# Power.net
KiCad netlist of a schematic drawn in Altium Designer
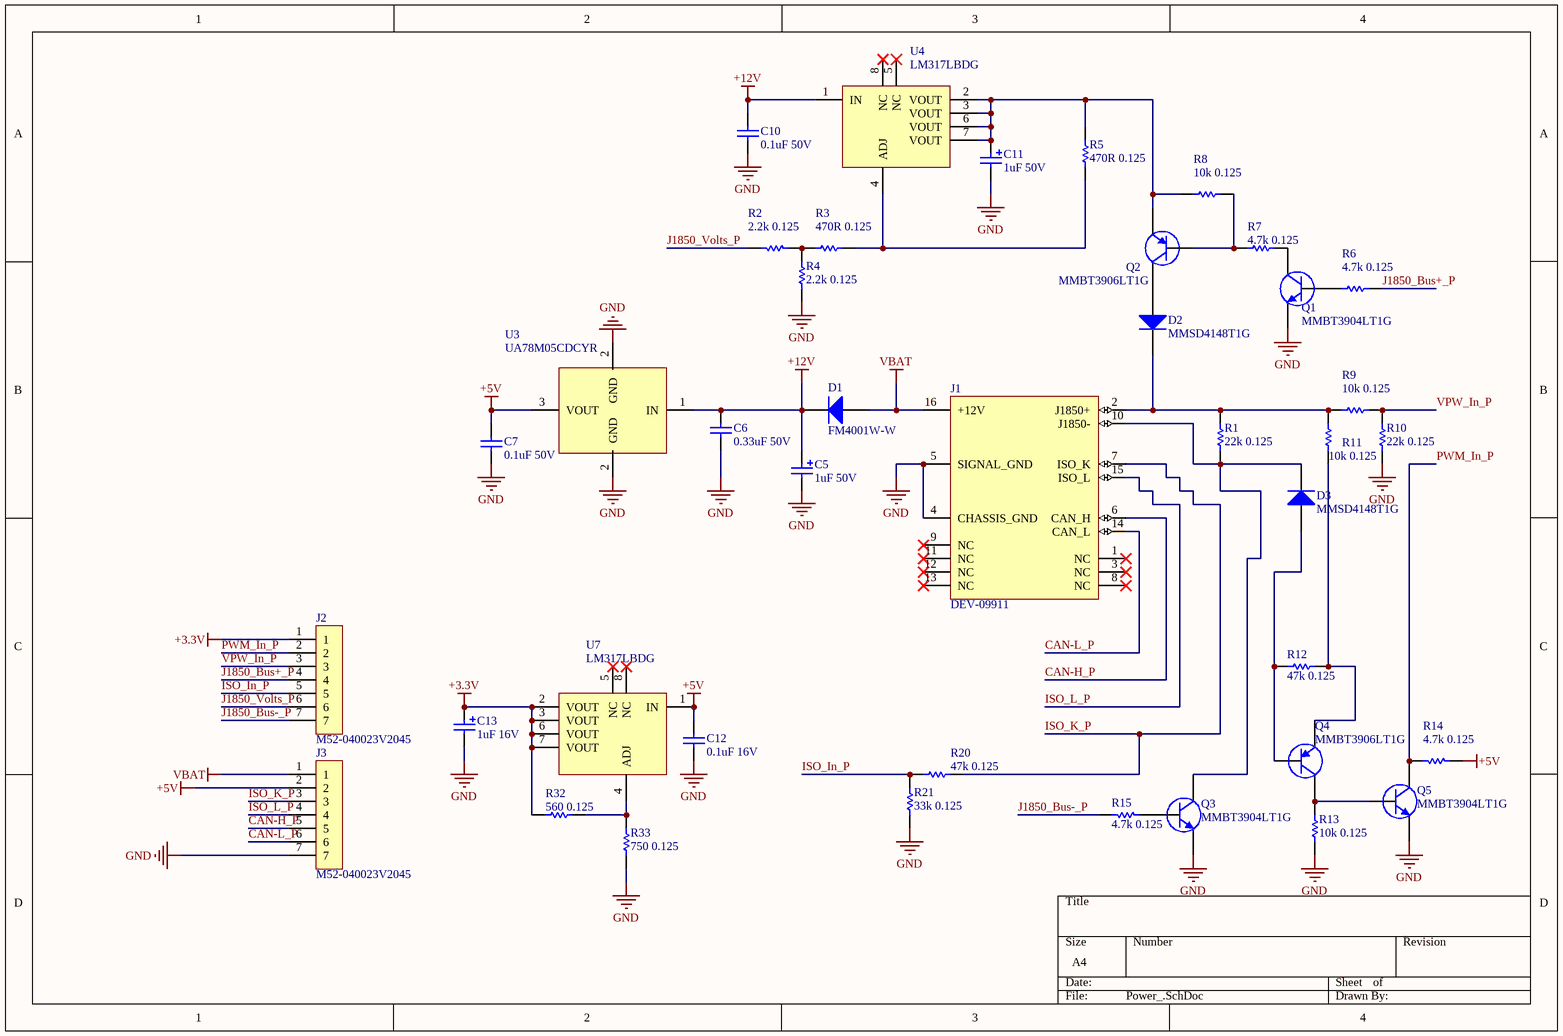
[diagram p0: Power_.SchDoc]

(export (version "E")
  (design (tool "Eeschema 10.0.6"))
  (components
    (comp (ref "C5")
      (value "1uF 50V")
      (footprint "C1005")
      (description "Surface-Mount Electrolitic Tantalum Capacitor, 1uF, 20% Tolerance, 1005 Size, 50V")
      (fields (field (name "PUBLISHER") "Altium Limited"))
      (libsource (lib "OBDII-components") (part "298D105X0050P2T"))
    )
    (comp (ref "C6")
      (value "0.33uF 50V")
      (footprint "1608[0603]")
      (description "Surface-Mount Ceramic Multilayer Capacitor, 0.33uF, 10% Tolerance, 0603 Size, 50V")
      (libsource (lib "OBDII-components") (part "C1608X7R1H334K080AC"))
    )
    (comp (ref "C7")
      (value "0.1uF 50V")
      (footprint "1608[0603]")
      (description "Surface-Mount Ceramic Multilayer Capacitor, 0.1uF, 10% Tolerance, 0603 Size, 50V")
      (libsource (lib "OBDII-components") (part "C0603C104K5RACTU"))
    )
    (comp (ref "C10")
      (value "0.1uF 50V")
      (footprint "1608[0603]")
      (description "Surface-Mount Ceramic Multilayer Capacitor, 0.1uF, 10% Tolerance, 0603 Size, 50V")
      (libsource (lib "OBDII-components") (part "C0603C104K5RACTU"))
    )
    (comp (ref "C11")
      (value "1uF 50V")
      (footprint "C1005")
      (description "Surface-Mount Electrolitic Tantalum Capacitor, 1uF, 20% Tolerance, 1005 Size, 50V")
      (fields (field (name "PUBLISHER") "Altium Limited"))
      (libsource (lib "OBDII-components") (part "298D105X0050P2T"))
    )
    (comp (ref "C12")
      (value "0.1uF 16V")
      (footprint "1608[0603]")
      (description "Surface-Mount Ceramic Multilayer Capacitor, 0.1uF, X5R, 10% Tolerance, 0603 Size, 16V")
      (fields (field (name "PUBLISHER") "Altium Limited"))
      (libsource (lib "OBDII-components") (part "GRM188R61C104KA01D"))
    )
    (comp (ref "C13")
      (value "1uF 16V")
      (footprint "C0603")
      (description "Surface-Mount Electrolitic Tantalum Capacitor, 1uF, 10% Tolerance, 0603 Size, 16V")
      (fields (field (name "PUBLISHER") "Altium Limited"))
      (libsource (lib "OBDII-components") (part "298D105X9016M2T"))
    )
    (comp (ref "D1")
      (value "FM4001W-W")
      (footprint "SMA,2.8mm")
      (description "1 Amp 50V  Rectifier")
      (libsource (lib "OBDII-components") (part "FM4001W-W"))
    )
    (comp (ref "D2")
      (value "MMSD4148T1G")
      (footprint "SOD123")
      (description "High Conductance Fast Diode")
      (fields
        (field (name "MANUFACTURER") "OnSemi")
        (field (name "PUBLISHER") "Vanteon")
        (field (name "APPROVED") "M. Jablonski")
      )
      (libsource (lib "OBDII-components") (part "MMSD4148T1G"))
    )
    (comp (ref "D3")
      (value "MMSD4148T1G")
      (footprint "SOD123")
      (description "High Conductance Fast Diode")
      (fields
        (field (name "MANUFACTURER") "OnSemi")
        (field (name "PUBLISHER") "Vanteon")
        (field (name "APPROVED") "M. Jablonski")
      )
      (libsource (lib "OBDII-components") (part "MMSD4148T1G"))
    )
    (comp (ref "J1")
      (value "DEV-09911")
      (footprint "DEV-09911 - II")
      (description "OBD-II Connector")
      (fields (field (name "MANUFACTURER") "SparkFun Electronics"))
      (libsource (lib "OBDII-components") (part "OBDII_DEV-09911"))
    )
    (comp (ref "J2")
      (value "M52-040023V2045")
      (footprint "M52-040023V2045")
      (description "CONN HEADER .050\" 50POS PCB GOLD")
      (fields (field (name "MANUFACTURER") "Harwin"))
      (libsource (lib "OBDII-components") (part "M52-040023V2045"))
    )
    (comp (ref "J3")
      (value "M52-040023V2045")
      (footprint "M52-040023V2045")
      (description "CONN HEADER .050\" 50POS PCB GOLD")
      (fields (field (name "MANUFACTURER") "Harwin"))
      (libsource (lib "OBDII-components") (part "M52-040023V2045"))
    )
    (comp (ref "Q1")
      (value "MMBT3904LT1G")
      (footprint "SOT23")
      (description "NPN 3904 General Purpose Amplifier")
      (fields
        (field (name "MANUFACTURER") "ON Semiconductor")
        (field (name "PUBLISHER") "Vanteon")
        (field (name "APPROVED") "Yes by Implemenation")
      )
      (libsource (lib "OBDII-components") (part "MMBT3904LT1G"))
    )
    (comp (ref "Q2")
      (value "MMBT3906LT1G")
      (footprint "SOT23")
      (description "PNP 3906 General Purpose Amplifier")
      (fields
        (field (name "MANUFACTURER") "ON Semiconductor")
        (field (name "PUBLISHER") "Vanteon")
        (field (name "APPROVED") "Yes by Implemenation")
      )
      (libsource (lib "OBDII-components") (part "MMBT3906LT1G"))
    )
    (comp (ref "Q3")
      (value "MMBT3904LT1G")
      (footprint "SOT23")
      (description "NPN 3904 General Purpose Amplifier")
      (fields
        (field (name "MANUFACTURER") "ON Semiconductor")
        (field (name "PUBLISHER") "Vanteon")
        (field (name "APPROVED") "Yes by Implemenation")
      )
      (libsource (lib "OBDII-components") (part "MMBT3904LT1G"))
    )
    (comp (ref "Q4")
      (value "MMBT3906LT1G")
      (footprint "SOT23")
      (description "PNP 3906 General Purpose Amplifier")
      (fields
        (field (name "MANUFACTURER") "ON Semiconductor")
        (field (name "PUBLISHER") "Vanteon")
        (field (name "APPROVED") "Yes by Implemenation")
      )
      (libsource (lib "OBDII-components") (part "MMBT3906LT1G"))
    )
    (comp (ref "Q5")
      (value "MMBT3904LT1G")
      (footprint "SOT23")
      (description "NPN 3904 General Purpose Amplifier")
      (fields
        (field (name "MANUFACTURER") "ON Semiconductor")
        (field (name "PUBLISHER") "Vanteon")
        (field (name "APPROVED") "Yes by Implemenation")
      )
      (libsource (lib "OBDII-components") (part "MMBT3904LT1G"))
    )
    (comp (ref "R1")
      (value "22k 0.125")
      (footprint "ERA-0805")
      (description "Rectangular Thick Film Chip Resistor, 22 kOhm, 0.1% Tolerance, 0805 Size, 0.125 W")
      (libsource (lib "OBDII-components") (part "ERA-6AEB223V"))
    )
    (comp (ref "R2")
      (value "2.2k 0.125")
      (footprint "ERA-0805")
      (description "Rectangular Thick Film Chip Resistor, 2.2 kOhm, 0.1% Tolerance, 0805 Size, 0.125 W")
      (libsource (lib "OBDII-components") (part "ERA-6AEB222V"))
    )
    (comp (ref "R3")
      (value "470R 0.125")
      (footprint "ERA-0805")
      (description "Rectangular Thick Film Chip Resistor, 470 Ohm, 0.1% Tolerance, 0805 Size, 0.125 W")
      (libsource (lib "OBDII-components") (part "ERA-6AEB471V"))
    )
    (comp (ref "R4")
      (value "2.2k 0.125")
      (footprint "ERA-0805")
      (description "Rectangular Thick Film Chip Resistor, 2.2 kOhm, 0.1% Tolerance, 0805 Size, 0.125 W")
      (libsource (lib "OBDII-components") (part "ERA-6AEB222V"))
    )
    (comp (ref "R5")
      (value "470R 0.125")
      (footprint "ERA-0805")
      (description "Rectangular Thick Film Chip Resistor, 470 Ohm, 0.1% Tolerance, 0805 Size, 0.125 W")
      (libsource (lib "OBDII-components") (part "ERA-6AEB471V"))
    )
    (comp (ref "R6")
      (value "4.7k 0.125")
      (footprint "ERA-0805")
      (description "Rectangular Thick Film Chip Resistor, 4.7 kOhm, 0.1% Tolerance, 0805 Size, 0.125 W")
      (libsource (lib "OBDII-components") (part "ERA-6AEB472V"))
    )
    (comp (ref "R7")
      (value "4.7k 0.125")
      (footprint "ERA-0805")
      (description "Rectangular Thick Film Chip Resistor, 4.7 kOhm, 0.1% Tolerance, 0805 Size, 0.125 W")
      (libsource (lib "OBDII-components") (part "ERA-6AEB472V"))
    )
    (comp (ref "R8")
      (value "10k 0.125")
      (footprint "ERA-0805")
      (description "Rectangular Thick Film Chip Resistor, 10 kOhm, 0.1% Tolerance, 0805 Size, 0.125 W")
      (libsource (lib "OBDII-components") (part "ERA-6AEB103V"))
    )
    (comp (ref "R9")
      (value "10k 0.125")
      (footprint "ERA-0805")
      (description "Rectangular Thick Film Chip Resistor, 10 kOhm, 0.1% Tolerance, 0805 Size, 0.125 W")
      (libsource (lib "OBDII-components") (part "ERA-6AEB103V"))
    )
    (comp (ref "R10")
      (value "22k 0.125")
      (footprint "ERA-0805")
      (description "Rectangular Thick Film Chip Resistor, 22 kOhm, 0.1% Tolerance, 0805 Size, 0.125 W")
      (libsource (lib "OBDII-components") (part "ERA-6AEB223V"))
    )
    (comp (ref "R11")
      (value "10k 0.125")
      (footprint "ERA-0805")
      (description "Rectangular Thick Film Chip Resistor, 10 kOhm, 0.1% Tolerance, 0805 Size, 0.125 W")
      (libsource (lib "OBDII-components") (part "ERA-6AEB103V"))
    )
    (comp (ref "R12")
      (value "47k 0.125")
      (footprint "ERA-0805")
      (description "Rectangular Thick Film Chip Resistor, 47 kOhm, 0.1% Tolerance, 0805 Size, 0.125 W")
      (libsource (lib "OBDII-components") (part "ERA-6AEB473V"))
    )
    (comp (ref "R13")
      (value "10k 0.125")
      (footprint "ERA-0805")
      (description "Rectangular Thick Film Chip Resistor, 10 kOhm, 0.1% Tolerance, 0805 Size, 0.125 W")
      (libsource (lib "OBDII-components") (part "ERA-6AEB103V"))
    )
    (comp (ref "R14")
      (value "4.7k 0.125")
      (footprint "ERA-0805")
      (description "Rectangular Thick Film Chip Resistor, 4.7 kOhm, 0.1% Tolerance, 0805 Size, 0.125 W")
      (libsource (lib "OBDII-components") (part "ERA-6AEB472V"))
    )
    (comp (ref "R15")
      (value "4.7k 0.125")
      (footprint "ERA-0805")
      (description "Rectangular Thick Film Chip Resistor, 4.7 kOhm, 0.1% Tolerance, 0805 Size, 0.125 W")
      (libsource (lib "OBDII-components") (part "ERA-6AEB472V"))
    )
    (comp (ref "R20")
      (value "47k 0.125")
      (footprint "ERA-0805")
      (description "Rectangular Thick Film Chip Resistor, 47 kOhm, 0.1% Tolerance, 0805 Size, 0.125 W")
      (libsource (lib "OBDII-components") (part "ERA-6AEB473V"))
    )
    (comp (ref "R21")
      (value "33k 0.125")
      (footprint "ERA-0805")
      (description "Rectangular Thick Film Chip Resistor, 33 kOhm, 0.1% Tolerance, 0805 Size, 0.125 W")
      (libsource (lib "OBDII-components") (part "ERA-6AEB333V"))
    )
    (comp (ref "R32")
      (value "560 0.125")
      (footprint "ERA-0805")
      (description "Rectangular Thick Film Chip Resistor, 560 Ohm, 1% Tolerance, 0805 Size, 0.125 W")
      (libsource (lib "OBDII-components") (part "ERJ-6ENF5600V"))
    )
    (comp (ref "R33")
      (value "750 0.125")
      (footprint "ERA-0805")
      (description "Rectangular Thick Film Chip Resistor, 750 Ohm, 1% Tolerance, 0805 Size, 0.125 W")
      (libsource (lib "OBDII-components") (part "ERJ-6ENF7500V"))
    )
    (comp (ref "U3")
      (value "UA78M05CDCYR")
      (footprint "SOT223_L")
      (description "3-terminal regulator 5V in SOT-223")
      (fields
        (field (name "MANUFACTURER") "Texas Instruments")
        (field (name "APPROVED") "Yes by Implementation")
      )
      (libsource (lib "OBDII-components") (part "UA78M05CDCYR"))
    )
    (comp (ref "U4")
      (value "LM317LBDG")
      (footprint "SOIC8N")
      (description "3-terminal adjustable regulator   1.2V-37V 0.1A SOIC8")
      (fields
        (field (name "MANUFACTURER") "National Semiconductor")
        (field (name "PUBLISHER") "Vanteon")
        (field (name "APPROVED") "Yes by Implementation")
      )
      (libsource (lib "") (part "LM317LBDG_1"))
    )
    (comp (ref "U7")
      (value "LM317LBDG")
      (footprint "SOIC8N")
      (description "3-terminal adjustable regulator   1.2V-37V 0.1A SOIC8")
      (fields
        (field (name "MANUFACTURER") "National Semiconductor")
        (field (name "PUBLISHER") "Vanteon")
        (field (name "APPROVED") "Yes by Implementation")
      )
      (libsource (lib "OBDII-components") (part "LM317LBDG"))
    )
  )
  (nets
    (net (code "1") (name "+3.3V") (class "Default")
      (node (ref "C13") (pin "1") (pinfunction "1_1") (pintype "passive"))
      (node (ref "J2") (pin "1") (pinfunction "1_1") (pintype "passive"))
      (node (ref "R32") (pin "1") (pinfunction "1_1") (pintype "passive"))
      (node (ref "U7") (pin "2") (pinfunction "VOUT_2") (pintype "passive"))
      (node (ref "U7") (pin "3") (pinfunction "VOUT_3") (pintype "passive"))
      (node (ref "U7") (pin "6") (pinfunction "VOUT_6") (pintype "passive"))
      (node (ref "U7") (pin "7") (pinfunction "VOUT_7") (pintype "passive"))
    )
    (net (code "2") (name "+5V") (class "Default")
      (node (ref "C12") (pin "2") (pinfunction "2_2") (pintype "passive"))
      (node (ref "C7") (pin "2") (pinfunction "2_2") (pintype "passive"))
      (node (ref "J3") (pin "2") (pinfunction "2_2") (pintype "passive"))
      (node (ref "R14") (pin "1") (pinfunction "1_1") (pintype "passive"))
      (node (ref "U3") (pin "3") (pinfunction "VOUT_3") (pintype "passive"))
      (node (ref "U7") (pin "1") (pinfunction "IN_1") (pintype "power_in"))
    )
    (net (code "3") (name "+12V") (class "Default")
      (node (ref "C10") (pin "2") (pinfunction "2_2") (pintype "passive"))
      (node (ref "C5") (pin "1") (pinfunction "1_1") (pintype "passive"))
      (node (ref "C6") (pin "2") (pinfunction "2_2") (pintype "passive"))
      (node (ref "D1") (pin "2") (pinfunction "K_2") (pintype "passive"))
      (node (ref "U3") (pin "1") (pinfunction "IN_1") (pintype "power_in"))
      (node (ref "U4") (pin "1") (pinfunction "IN_1") (pintype "power_in"))
    )
    (net (code "4") (name "/CAN-H_P") (class "Default")
      (node (ref "J1") (pin "6") (pinfunction "CAN_H_6") (pintype "bidirectional"))
      (node (ref "J3") (pin "5") (pinfunction "5_5") (pintype "passive"))
    )
    (net (code "5") (name "/CAN-L_P") (class "Default")
      (node (ref "J1") (pin "14") (pinfunction "CAN_L_14") (pintype "bidirectional"))
      (node (ref "J3") (pin "6") (pinfunction "6_6") (pintype "passive"))
    )
    (net (code "6") (name "/ISO_In_P") (class "Default")
      (node (ref "J2") (pin "5") (pinfunction "5_5") (pintype "passive"))
      (node (ref "R20") (pin "1") (pinfunction "1_1") (pintype "passive"))
      (node (ref "R21") (pin "2") (pinfunction "2_2") (pintype "passive"))
    )
    (net (code "7") (name "/ISO_K_P") (class "Default")
      (node (ref "J1") (pin "7") (pinfunction "ISO_K_7") (pintype "bidirectional"))
      (node (ref "J3") (pin "3") (pinfunction "3_3") (pintype "passive"))
      (node (ref "R20") (pin "2") (pinfunction "2_2") (pintype "passive"))
    )
    (net (code "8") (name "/ISO_L_P") (class "Default")
      (node (ref "J1") (pin "15") (pinfunction "ISO_L_15") (pintype "bidirectional"))
      (node (ref "J3") (pin "4") (pinfunction "4_4") (pintype "passive"))
    )
    (net (code "9") (name "/J1850_Bus+_P") (class "Default")
      (node (ref "J2") (pin "4") (pinfunction "4_4") (pintype "passive"))
      (node (ref "R6") (pin "2") (pinfunction "2_2") (pintype "passive"))
    )
    (net (code "10") (name "/J1850_Bus-_P") (class "Default")
      (node (ref "J2") (pin "7") (pinfunction "7_7") (pintype "passive"))
      (node (ref "R15") (pin "2") (pinfunction "2_2") (pintype "passive"))
    )
    (net (code "11") (name "/J1850_Volts_P") (class "Default")
      (node (ref "J2") (pin "6") (pinfunction "6_6") (pintype "passive"))
      (node (ref "R2") (pin "2") (pinfunction "2_2") (pintype "passive"))
    )
    (net (code "12") (name "/PWM_In_P") (class "Default")
      (node (ref "J2") (pin "2") (pinfunction "2_2") (pintype "passive"))
      (node (ref "Q5") (pin "3") (pinfunction "C_3") (pintype "passive"))
      (node (ref "R14") (pin "2") (pinfunction "2_2") (pintype "passive"))
    )
    (net (code "13") (name "/VPW_In_P") (class "Default")
      (node (ref "J2") (pin "3") (pinfunction "3_3") (pintype "passive"))
      (node (ref "R10") (pin "2") (pinfunction "2_2") (pintype "passive"))
      (node (ref "R9") (pin "1") (pinfunction "1_1") (pintype "passive"))
    )
    (net (code "14") (name "GND") (class "Default")
      (node (ref "C10") (pin "1") (pinfunction "1_1") (pintype "passive"))
      (node (ref "C11") (pin "2") (pinfunction "2_2") (pintype "passive"))
      (node (ref "C12") (pin "1") (pinfunction "1_1") (pintype "passive"))
      (node (ref "C13") (pin "2") (pinfunction "2_2") (pintype "passive"))
      (node (ref "C6") (pin "1") (pinfunction "1_1") (pintype "passive"))
      (node (ref "C7") (pin "1") (pinfunction "1_1") (pintype "passive"))
      (node (ref "J1") (pin "4") (pinfunction "CHASSIS_GND_4") (pintype "power_in"))
      (node (ref "J1") (pin "5") (pinfunction "SIGNAL_GND_5") (pintype "power_in"))
      (node (ref "J3") (pin "7") (pinfunction "7_7") (pintype "passive"))
      (node (ref "Q1") (pin "2") (pinfunction "E_2") (pintype "passive"))
      (node (ref "Q3") (pin "2") (pinfunction "E_2") (pintype "passive"))
      (node (ref "Q5") (pin "2") (pinfunction "E_2") (pintype "passive"))
      (node (ref "R10") (pin "1") (pinfunction "1_1") (pintype "passive"))
      (node (ref "R13") (pin "2") (pinfunction "2_2") (pintype "passive"))
      (node (ref "R21") (pin "1") (pinfunction "1_1") (pintype "passive"))
      (node (ref "R33") (pin "1") (pinfunction "1_1") (pintype "passive"))
      (node (ref "R4") (pin "1") (pinfunction "1_1") (pintype "passive"))
      (node (ref "U3") (pin "2") (pinfunction "GND_2") (pintype "power_in"))
    )
    (net (code "15") (name "Net-(D2-A)") (class "Default")
      (node (ref "D2") (pin "1") (pinfunction "A_1") (pintype "passive"))
      (node (ref "Q2") (pin "3") (pinfunction "C_3") (pintype "passive"))
    )
    (net (code "16") (name "Net-(D2-C)") (class "Default")
      (node (ref "D2") (pin "2") (pinfunction "C_2") (pintype "passive"))
      (node (ref "J1") (pin "2") (pinfunction "J1850+_2") (pintype "bidirectional"))
      (node (ref "R1") (pin "2") (pinfunction "2_2") (pintype "passive"))
      (node (ref "R11") (pin "1") (pinfunction "1_1") (pintype "passive"))
      (node (ref "R9") (pin "2") (pinfunction "2_2") (pintype "passive"))
    )
    (net (code "17") (name "Net-(D3-A)") (class "Default")
      (node (ref "D3") (pin "1") (pinfunction "A_1") (pintype "passive"))
      (node (ref "Q4") (pin "1") (pinfunction "B_1") (pintype "passive"))
      (node (ref "R12") (pin "1") (pinfunction "1_1") (pintype "passive"))
    )
    (net (code "18") (name "Net-(D3-C)") (class "Default")
      (node (ref "D3") (pin "2") (pinfunction "C_2") (pintype "passive"))
      (node (ref "J1") (pin "10") (pinfunction "J1850-_10") (pintype "bidirectional"))
      (node (ref "Q3") (pin "3") (pinfunction "C_3") (pintype "passive"))
      (node (ref "R1") (pin "1") (pinfunction "1_1") (pintype "passive"))
    )
    (net (code "19") (name "Net-(Q1-B)") (class "Default")
      (node (ref "Q1") (pin "1") (pinfunction "B_1") (pintype "passive"))
      (node (ref "R6") (pin "1") (pinfunction "1_1") (pintype "passive"))
    )
    (net (code "20") (name "Net-(Q1-C)") (class "Default")
      (node (ref "Q1") (pin "3") (pinfunction "C_3") (pintype "passive"))
      (node (ref "R7") (pin "2") (pinfunction "2_2") (pintype "passive"))
    )
    (net (code "21") (name "Net-(Q2-B)") (class "Default")
      (node (ref "Q2") (pin "1") (pinfunction "B_1") (pintype "passive"))
      (node (ref "R7") (pin "1") (pinfunction "1_1") (pintype "passive"))
      (node (ref "R8") (pin "1") (pinfunction "1_1") (pintype "passive"))
    )
    (net (code "22") (name "Net-(Q2-E)") (class "Default")
      (node (ref "C11") (pin "1") (pinfunction "1_1") (pintype "passive"))
      (node (ref "Q2") (pin "2") (pinfunction "E_2") (pintype "passive"))
      (node (ref "R5") (pin "2") (pinfunction "2_2") (pintype "passive"))
      (node (ref "R8") (pin "2") (pinfunction "2_2") (pintype "passive"))
      (node (ref "U4") (pin "2") (pinfunction "VOUT_2") (pintype "passive"))
      (node (ref "U4") (pin "3") (pinfunction "VOUT_3") (pintype "passive"))
      (node (ref "U4") (pin "6") (pinfunction "VOUT_6") (pintype "passive"))
      (node (ref "U4") (pin "7") (pinfunction "VOUT_7") (pintype "passive"))
    )
    (net (code "23") (name "Net-(Q3-B)") (class "Default")
      (node (ref "Q3") (pin "1") (pinfunction "B_1") (pintype "passive"))
      (node (ref "R15") (pin "1") (pinfunction "1_1") (pintype "passive"))
    )
    (net (code "24") (name "Net-(Q4-C)") (class "Default")
      (node (ref "Q4") (pin "3") (pinfunction "C_3") (pintype "passive"))
      (node (ref "Q5") (pin "1") (pinfunction "B_1") (pintype "passive"))
      (node (ref "R13") (pin "1") (pinfunction "1_1") (pintype "passive"))
    )
    (net (code "25") (name "Net-(Q4-E)") (class "Default")
      (node (ref "Q4") (pin "2") (pinfunction "E_2") (pintype "passive"))
      (node (ref "R11") (pin "2") (pinfunction "2_2") (pintype "passive"))
      (node (ref "R12") (pin "2") (pinfunction "2_2") (pintype "passive"))
    )
    (net (code "26") (name "Net-(R2-Pad1)") (class "Default")
      (node (ref "R2") (pin "1") (pinfunction "1_1") (pintype "passive"))
      (node (ref "R3") (pin "2") (pinfunction "2_2") (pintype "passive"))
      (node (ref "R4") (pin "2") (pinfunction "2_2") (pintype "passive"))
    )
    (net (code "27") (name "Net-(U4-ADJ)") (class "Default")
      (node (ref "R3") (pin "1") (pinfunction "1_1") (pintype "passive"))
      (node (ref "R5") (pin "1") (pinfunction "1_1") (pintype "passive"))
      (node (ref "U4") (pin "4") (pinfunction "ADJ_4") (pintype "power_in"))
    )
    (net (code "28") (name "Net-(U7-ADJ)") (class "Default")
      (node (ref "R32") (pin "2") (pinfunction "2_2") (pintype "passive"))
      (node (ref "R33") (pin "2") (pinfunction "2_2") (pintype "passive"))
      (node (ref "U7") (pin "4") (pinfunction "ADJ_4") (pintype "power_in"))
    )
    (net (code "29") (name "VBAT") (class "Default")
      (node (ref "D1") (pin "1") (pinfunction "A_1") (pintype "passive"))
      (node (ref "J1") (pin "16") (pinfunction "+12V_16") (pintype "power_in"))
      (node (ref "J3") (pin "1") (pinfunction "1_1") (pintype "passive"))
    )
    (net (code "30") (name "unconnected-(C5-Pad2)") (class "Default")
      (node (ref "C5") (pin "2") (pinfunction "2_2") (pintype "passive"))
    )
    (net (code "31") (name "unconnected-(J1-NC-Pad1)") (class "Default")
      (node (ref "J1") (pin "1") (pinfunction "NC_1") (pintype "passive+no_connect"))
    )
    (net (code "32") (name "unconnected-(J1-NC-Pad3)") (class "Default")
      (node (ref "J1") (pin "3") (pinfunction "NC_3") (pintype "passive+no_connect"))
    )
    (net (code "33") (name "unconnected-(J1-NC-Pad8)") (class "Default")
      (node (ref "J1") (pin "8") (pinfunction "NC_8") (pintype "passive+no_connect"))
    )
    (net (code "34") (name "unconnected-(J1-NC-Pad9)") (class "Default")
      (node (ref "J1") (pin "9") (pinfunction "NC_9") (pintype "passive+no_connect"))
    )
    (net (code "35") (name "unconnected-(J1-NC-Pad11)") (class "Default")
      (node (ref "J1") (pin "11") (pinfunction "NC_11") (pintype "passive+no_connect"))
    )
    (net (code "36") (name "unconnected-(J1-NC-Pad12)") (class "Default")
      (node (ref "J1") (pin "12") (pinfunction "NC_12") (pintype "passive+no_connect"))
    )
    (net (code "37") (name "unconnected-(J1-NC-Pad13)") (class "Default")
      (node (ref "J1") (pin "13") (pinfunction "NC_13") (pintype "passive+no_connect"))
    )
    (net (code "38") (name "unconnected-(U4-NC-Pad5)") (class "Default")
      (node (ref "U4") (pin "5") (pinfunction "NC_5") (pintype "passive+no_connect"))
    )
    (net (code "39") (name "unconnected-(U4-NC-Pad8)") (class "Default")
      (node (ref "U4") (pin "8") (pinfunction "NC_8") (pintype "passive+no_connect"))
    )
    (net (code "40") (name "unconnected-(U7-NC-Pad5)") (class "Default")
      (node (ref "U7") (pin "5") (pinfunction "NC_5") (pintype "passive+no_connect"))
    )
    (net (code "41") (name "unconnected-(U7-NC-Pad8)") (class "Default")
      (node (ref "U7") (pin "8") (pinfunction "NC_8") (pintype "passive+no_connect"))
    )
  )
)
